# 2_power.net
KiCad netlist of a schematic drawn in Altium Designer
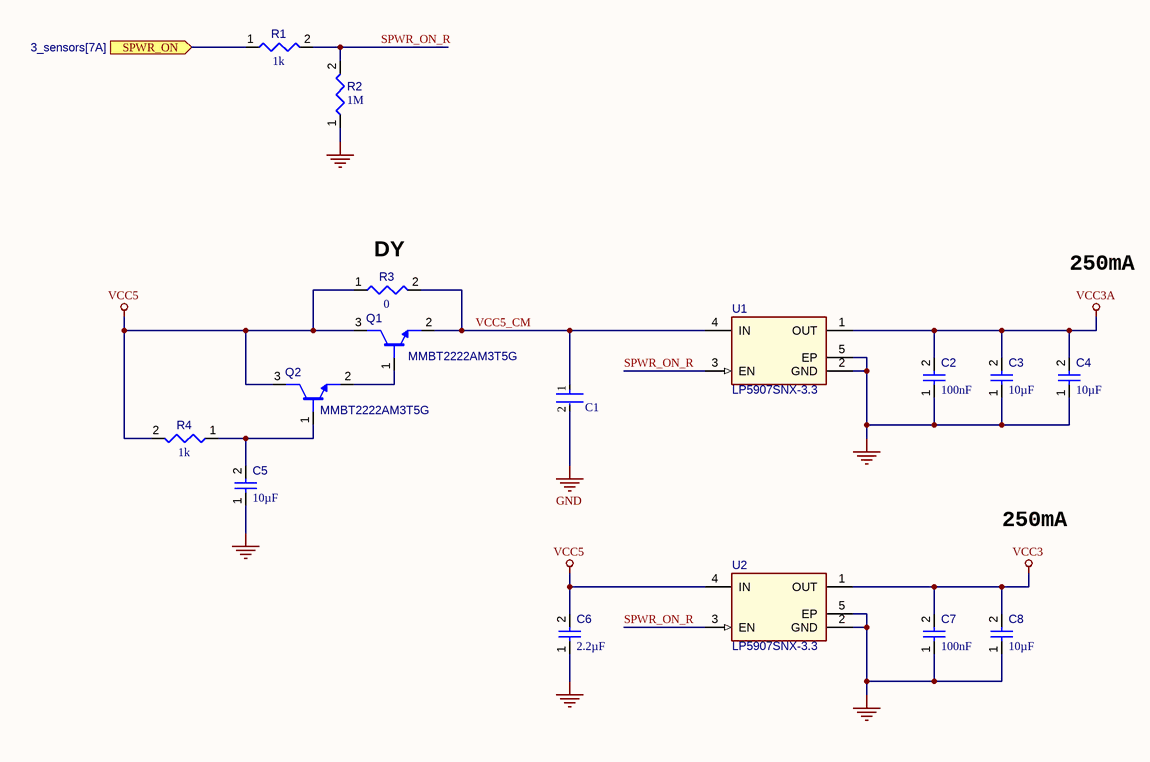
[diagram p0: 2_power.SchDoc]

(export (version "E")
  (design (tool "Eeschema 10.0.6"))
  (components
    (comp (ref "C1")
      (value "0805ZD225KAT2A")
      (footprint "FP-0805-L_2_01_0_2-W_1_25-IPC_B")
      (libsource (lib "SKA- Automa玢o de Engenharias") (part "b4654b650e69147ec39a6b967a45e02"))
    )
    (comp (ref "C2")
      (value "100nF")
      (footprint "CAPC0402(1005)60_L")
      (description "Chip Capacitor, 100nF +/-20%, 10V, 0402, Thickness 0.6 mm")
      (fields (field (name "TOLERANCE") "20%") (field (name "Comment") "Capacitor 100nF +/-20% 10V 0402"))
      (libsource (lib "SKA- Automa玢o de Engenharias") (part "CAP-NP-2"))
    )
    (comp (ref "C3")
      (value "10µF")
      (footprint "CAPC0402(1005)60_L")
      (description "Chip Capacitor, 10µF +/-40%, 6.3V, 0402, Thickness 0.6 mm")
      (fields (field (name "TOLERANCE") "10%") (field (name "Comment") "Capacitor 10µF +/-40% 6.3V 0402"))
      (libsource (lib "SKA- Automa玢o de Engenharias") (part "CAP-NP-2"))
    )
    (comp (ref "C4")
      (value "10µF")
      (footprint "CAPC0402(1005)60_L")
      (description "Chip Capacitor, 10µF +/-40%, 6.3V, 0402, Thickness 0.6 mm")
      (fields (field (name "TOLERANCE") "10%") (field (name "Comment") "Capacitor 10µF +/-40% 6.3V 0402"))
      (libsource (lib "SKA- Automa玢o de Engenharias") (part "CAP-NP-2"))
    )
    (comp (ref "C5")
      (value "10µF")
      (footprint "CAPC0402(1005)60_L")
      (description "Chip Capacitor, 10µF +/-40%, 6.3V, 0402, Thickness 0.6 mm")
      (fields (field (name "TOLERANCE") "10%") (field (name "Comment") "Capacitor 10µF +/-40% 6.3V 0402"))
      (libsource (lib "SKA- Automa玢o de Engenharias") (part "CAP-NP-2"))
    )
    (comp (ref "C6")
      (value "2.2µF")
      (footprint "CAPC0402(1005)60_L")
      (description "Chip Capacitor, 2,2µF +/-20%, 10V, 0402, Thickness 0.6 mm")
      (fields (field (name "TOLERANCE") "10%") (field (name "Comment") "Capacitor 2,2µF +/-20% 10V 0402"))
      (libsource (lib "SKA- Automa玢o de Engenharias") (part "CAP-NP-2"))
    )
    (comp (ref "C7")
      (value "100nF")
      (footprint "CAPC0402(1005)60_L")
      (description "Chip Capacitor, 100nF +/-20%, 10V, 0402, Thickness 0.6 mm")
      (fields (field (name "TOLERANCE") "20%") (field (name "Comment") "Capacitor 100nF +/-20% 10V 0402"))
      (libsource (lib "SKA- Automa玢o de Engenharias") (part "CAP-NP-2"))
    )
    (comp (ref "C8")
      (value "10µF")
      (footprint "CAPC0402(1005)60_L")
      (description "Chip Capacitor, 10µF +/-40%, 6.3V, 0402, Thickness 0.6 mm")
      (fields (field (name "TOLERANCE") "10%") (field (name "Comment") "Capacitor 10µF +/-40% 6.3V 0402"))
      (libsource (lib "SKA- Automa玢o de Engenharias") (part "CAP-NP-2"))
    )
    (comp (ref "Q1")
      (value "MMBT2222AM3T5G")
      (footprint "ROHM-SOT723-3_V")
      (description "NPN General Purpose Transistor, 3-Pin SOT-723, Pb-Free, Tape and Reel")
      (libsource (lib "<Company> Server") (part "CMP-00026-6"))
    )
    (comp (ref "Q2")
      (value "MMBT2222AM3T5G")
      (footprint "ROHM-SOT723-3_V")
      (description "NPN General Purpose Transistor, 3-Pin SOT-723, Pb-Free, Tape and Reel")
      (libsource (lib "<Company> Server") (part "CMP-00026-6"))
    )
    (comp (ref "R1")
      (value "1k")
      (footprint "RESC0402(1005)_L")
      (description "Chip Resistor, 1 kOhms, +/-5 %, 63 mW, -55 to 155 degC, 0402")
      (fields (field (name "POWER") "63mW") (field (name "TOLERANCE") "5%"))
      (libsource (lib "SKA- Automa玢o de Engenharias") (part "RES-2"))
    )
    (comp (ref "R2")
      (value "1M")
      (footprint "RESC0402(1005)_L")
      (description "Chip Resistor, 1 MOhms, +/-5 %, 63 mW, -55 to 155 degC, 0402")
      (fields (field (name "POWER") "63mW") (field (name "TOLERANCE") "5%"))
      (libsource (lib "SKA- Automa玢o de Engenharias") (part "RES-2"))
    )
    (comp (ref "R3")
      (value "0")
      (footprint "RESC0402(1005)_L")
      (description "Jumper 0402")
      (libsource (lib "SKA- Automa玢o de Engenharias") (part "RES-2"))
    )
    (comp (ref "R4")
      (value "1k")
      (footprint "RESC0402(1005)_L")
      (description "Chip Resistor, 1 kOhms, +/-5 %, 63 mW, -55 to 155 degC, 0402")
      (fields (field (name "POWER") "63mW") (field (name "TOLERANCE") "5%"))
      (libsource (lib "SKA- Automa玢o de Engenharias") (part "RES-2"))
    )
    (comp (ref "U1")
      (value "LP5907SNX-3.3")
      (footprint "TI-DQN4-480X480TP_V")
      (description "Ultra-Low-Noise, Low-IQ LDO, 3.3 V, 0.25 A, -40 to 125 degC, 4-Pin X2SON, RoHS, Tape and Reel")
      (libsource (lib "SKA- Automa玢o de Engenharias") (part "CMP-00094-7"))
    )
    (comp (ref "U2")
      (value "LP5907SNX-3.3")
      (footprint "TI-DQN4-480X480TP_V")
      (description "Ultra-Low-Noise, Low-IQ LDO, 3.3 V, 0.25 A, -40 to 125 degC, 4-Pin X2SON, RoHS, Tape and Reel")
      (libsource (lib "SKA- Automa玢o de Engenharias") (part "CMP-00094-7"))
    )
  )
  (nets
    (net (code "1") (name "/SPWR_ON") (class "Default")
      (node (ref "R1") (pin "1") (pinfunction "1_1") (pintype "passive"))
    )
    (net (code "2") (name "/SPWR_ON_R") (class "Default")
      (node (ref "R1") (pin "2") (pinfunction "2_2") (pintype "passive"))
      (node (ref "R2") (pin "2") (pinfunction "2_2") (pintype "passive"))
      (node (ref "U1") (pin "3") (pinfunction "EN_3") (pintype "input"))
      (node (ref "U2") (pin "3") (pinfunction "EN_3") (pintype "input"))
    )
    (net (code "3") (name "/VCC5_CM") (class "Default")
      (node (ref "C1") (pin "1") (pinfunction "1_1") (pintype "passive"))
      (node (ref "Q1") (pin "2") (pinfunction "E_2") (pintype "passive"))
      (node (ref "R3") (pin "2") (pinfunction "2_2") (pintype "passive"))
      (node (ref "U1") (pin "4") (pinfunction "IN_4") (pintype "power_in"))
    )
    (net (code "4") (name "GND") (class "Default")
      (node (ref "C1") (pin "2") (pinfunction "2_2") (pintype "passive"))
      (node (ref "C2") (pin "1") (pinfunction "1_1") (pintype "passive"))
      (node (ref "C3") (pin "1") (pinfunction "1_1") (pintype "passive"))
      (node (ref "C4") (pin "1") (pinfunction "1_1") (pintype "passive"))
      (node (ref "C5") (pin "1") (pinfunction "1_1") (pintype "passive"))
      (node (ref "C6") (pin "1") (pinfunction "1_1") (pintype "passive"))
      (node (ref "C7") (pin "1") (pinfunction "1_1") (pintype "passive"))
      (node (ref "C8") (pin "1") (pinfunction "1_1") (pintype "passive"))
      (node (ref "R2") (pin "1") (pinfunction "1_1") (pintype "passive"))
      (node (ref "U1") (pin "2") (pinfunction "GND_2") (pintype "power_in"))
      (node (ref "U1") (pin "5") (pinfunction "EP_5") (pintype "power_in"))
      (node (ref "U2") (pin "2") (pinfunction "GND_2") (pintype "power_in"))
      (node (ref "U2") (pin "5") (pinfunction "EP_5") (pintype "power_in"))
    )
    (net (code "5") (name "Net-(Q1-B)") (class "Default")
      (node (ref "Q1") (pin "1") (pinfunction "B_1") (pintype "passive"))
      (node (ref "Q2") (pin "2") (pinfunction "E_2") (pintype "passive"))
    )
    (net (code "6") (name "Net-(Q2-B)") (class "Default")
      (node (ref "C5") (pin "2") (pinfunction "2_2") (pintype "passive"))
      (node (ref "Q2") (pin "1") (pinfunction "B_1") (pintype "passive"))
      (node (ref "R4") (pin "1") (pinfunction "1_1") (pintype "passive"))
    )
    (net (code "7") (name "VCC3") (class "Default")
      (node (ref "C7") (pin "2") (pinfunction "2_2") (pintype "passive"))
      (node (ref "C8") (pin "2") (pinfunction "2_2") (pintype "passive"))
      (node (ref "U2") (pin "1") (pinfunction "OUT_1") (pintype "power_in"))
    )
    (net (code "8") (name "VCC3A") (class "Default")
      (node (ref "C2") (pin "2") (pinfunction "2_2") (pintype "passive"))
      (node (ref "C3") (pin "2") (pinfunction "2_2") (pintype "passive"))
      (node (ref "C4") (pin "2") (pinfunction "2_2") (pintype "passive"))
      (node (ref "U1") (pin "1") (pinfunction "OUT_1") (pintype "power_in"))
    )
    (net (code "9") (name "VCC5") (class "Default")
      (node (ref "C6") (pin "2") (pinfunction "2_2") (pintype "passive"))
      (node (ref "Q1") (pin "3") (pinfunction "C_3") (pintype "passive"))
      (node (ref "Q2") (pin "3") (pinfunction "C_3") (pintype "passive"))
      (node (ref "R3") (pin "1") (pinfunction "1_1") (pintype "passive"))
      (node (ref "R4") (pin "2") (pinfunction "2_2") (pintype "passive"))
      (node (ref "U2") (pin "4") (pinfunction "IN_4") (pintype "power_in"))
    )
  )
)
